# Feedback_Controller_Buck.net
KiCad netlist of a schematic drawn in Altium Designer
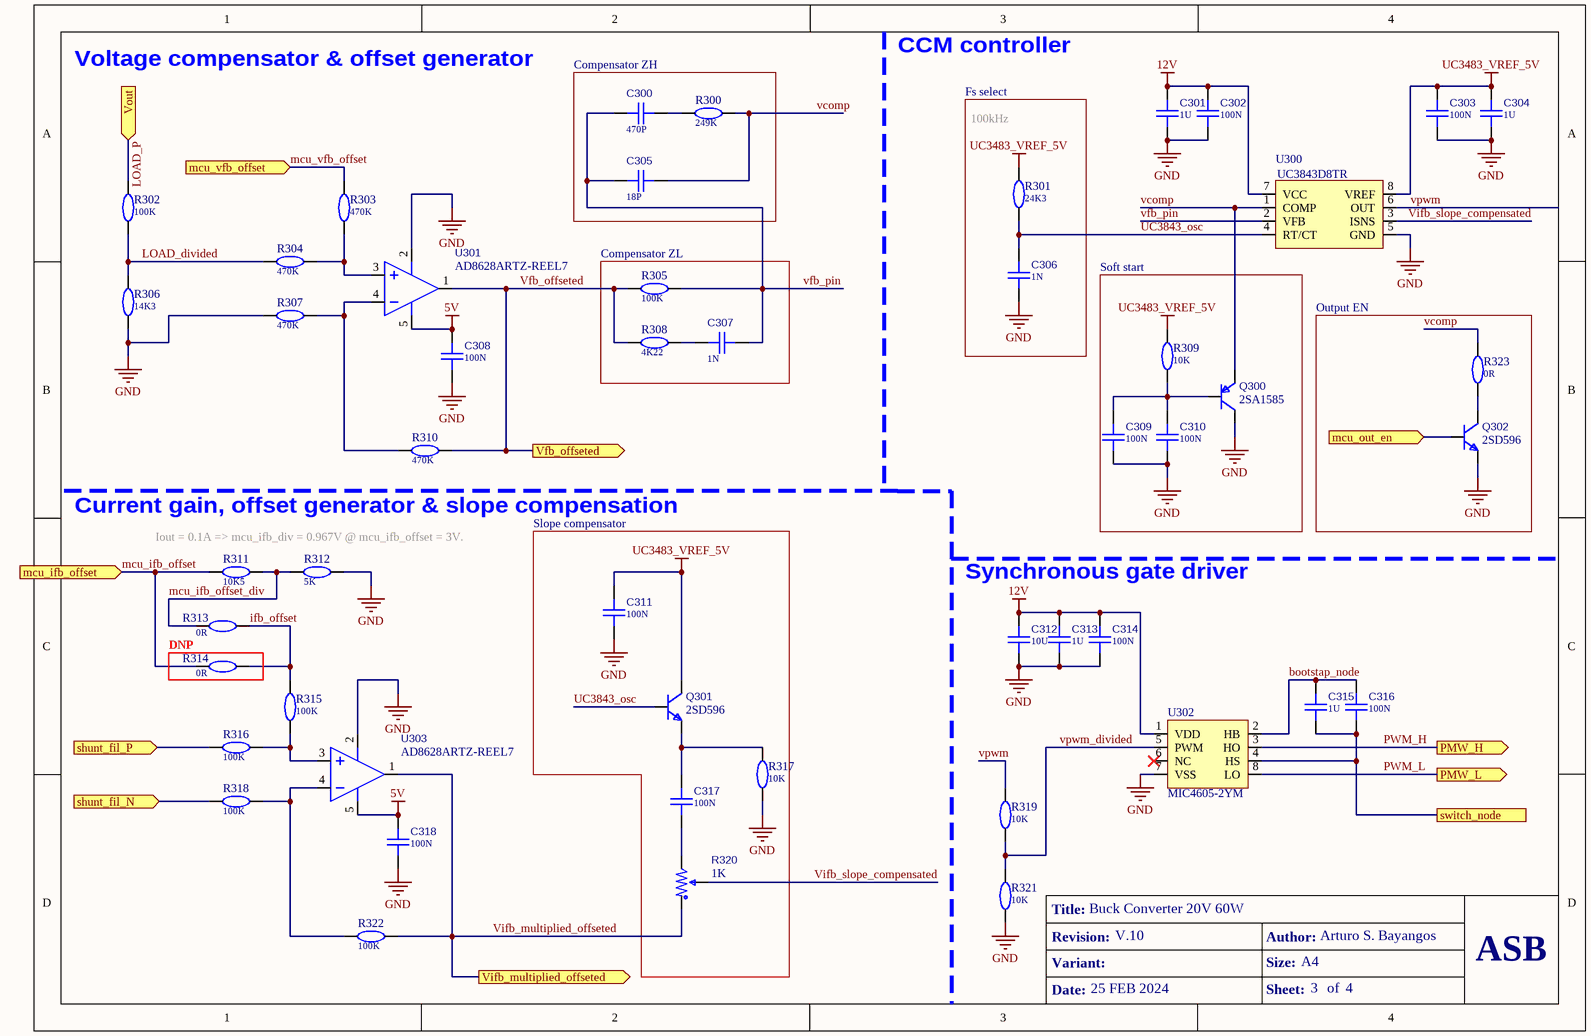
[diagram p0: Feedback_Controller_Buck.SchDoc]

(export (version "E")
  (design (tool "Eeschema 10.0.6"))
  (components
    (comp (ref "C300")
      (value "470P")
      (footprint "CAP_0603")
      (description "CAP 470P 0603 NPO 50V 2%")
      (fields (field (name "PART NUMBER") "CC0603GRNPO9BN471") (field (name "Comment") "CAPACITOR"))
      (libsource (lib "Altium_Library") (part "CAPACITOR"))
    )
    (comp (ref "C301")
      (value "1U")
      (footprint "CAP_0603")
      (description "CAP 1U 0603 X7R 25V 10%")
      (fields (field (name "PART NUMBER") "TMK107AB7105KAHT") (field (name "Comment") "CAPACITOR"))
      (libsource (lib "Altium_Library") (part "CAPACITOR"))
    )
    (comp (ref "C302")
      (value "100N")
      (footprint "CAP_0402")
      (description "CAP 100N 0402 X7R 50V 10%")
      (fields (field (name "PART NUMBER") "UMK105B7104KV-FR") (field (name "Comment") "CAPACITOR"))
      (libsource (lib "Altium_Library") (part "CAPACITOR"))
    )
    (comp (ref "C303")
      (value "100N")
      (footprint "CAP_0402")
      (description "CAP 100N 0402 X7R 50V 10%")
      (fields (field (name "PART NUMBER") "UMK105B7104KV-FR") (field (name "Comment") "CAPACITOR"))
      (libsource (lib "Altium_Library") (part "CAPACITOR"))
    )
    (comp (ref "C304")
      (value "1U")
      (footprint "CAP_0603")
      (description "CAP 1U 0603 X7R 25V 10%")
      (fields (field (name "PART NUMBER") "TMK107AB7105KAHT") (field (name "Comment") "CAPACITOR"))
      (libsource (lib "Altium_Library") (part "CAPACITOR"))
    )
    (comp (ref "C305")
      (value "18P")
      (footprint "CAP_0603")
      (description "CAP 18P 0603 NPO 50V 5%")
      (fields (field (name "PART NUMBER") "CC0603JRNPO9BN180") (field (name "Comment") "CAPACITOR"))
      (libsource (lib "Altium_Library") (part "CAPACITOR"))
    )
    (comp (ref "C306")
      (value "1N")
      (footprint "CAP_0603")
      (description "CAP 1N 0603 NPO 25V 2%")
      (fields (field (name "PART NUMBER") "CC0603GRNPO8BN102") (field (name "Comment") "CAPACITOR"))
      (libsource (lib "Altium_Library") (part "CAPACITOR"))
    )
    (comp (ref "C307")
      (value "1N")
      (footprint "CAP_0603")
      (description "CAP 1N 0603 NPO 25V 2%")
      (fields (field (name "PART NUMBER") "CC0603GRNPO8BN102") (field (name "Comment") "CAPACITOR"))
      (libsource (lib "Altium_Library") (part "CAPACITOR"))
    )
    (comp (ref "C308")
      (value "100N")
      (footprint "CAP_0402")
      (description "CAP 100N 0402 X7R 50V 10%")
      (fields (field (name "PART NUMBER") "UMK105B7104KV-FR") (field (name "Comment") "CAPACITOR"))
      (libsource (lib "Altium_Library") (part "CAPACITOR"))
    )
    (comp (ref "C309")
      (value "100N")
      (footprint "CAP_0402")
      (description "CAP 100N 0402 X7R 50V 10%")
      (fields (field (name "PART NUMBER") "UMK105B7104KV-FR") (field (name "Comment") "CAPACITOR"))
      (libsource (lib "Altium_Library") (part "CAPACITOR"))
    )
    (comp (ref "C310")
      (value "100N")
      (footprint "CAP_0402")
      (description "CAP 100N 0402 X7R 50V 10%")
      (fields (field (name "PART NUMBER") "UMK105B7104KV-FR") (field (name "Comment") "CAPACITOR"))
      (libsource (lib "Altium_Library") (part "CAPACITOR"))
    )
    (comp (ref "C311")
      (value "100N")
      (footprint "CAP_0402")
      (description "CAP 100N 0402 X7R 50V 10%")
      (fields (field (name "PART NUMBER") "UMK105B7104KV-FR") (field (name "Comment") "CAPACITOR"))
      (libsource (lib "Altium_Library") (part "CAPACITOR"))
    )
    (comp (ref "C312")
      (value "10U")
      (footprint "CAP_1210")
      (description "CAP 10U 1210 X7R 50V 10%")
      (fields (field (name "PART NUMBER") "UMK325AB7106KM-T") (field (name "Comment") "CAPACITOR"))
      (libsource (lib "Altium_Library") (part "CAPACITOR"))
    )
    (comp (ref "C313")
      (value "1U")
      (footprint "CAP_0603")
      (description "CAP 1U 0603 X7R 25V 10%")
      (fields (field (name "PART NUMBER") "TMK107AB7105KAHT") (field (name "Comment") "CAPACITOR"))
      (libsource (lib "Altium_Library") (part "CAPACITOR"))
    )
    (comp (ref "C314")
      (value "100N")
      (footprint "CAP_0402")
      (description "CAP 100N 0402 X7R 50V 10%")
      (fields (field (name "PART NUMBER") "UMK105B7104KV-FR") (field (name "Comment") "CAPACITOR"))
      (libsource (lib "Altium_Library") (part "CAPACITOR"))
    )
    (comp (ref "C315")
      (value "1U")
      (footprint "CAP_0603")
      (description "CAP 1U 0603 X7R 25V 10%")
      (fields (field (name "PART NUMBER") "TMK107AB7105KAHT") (field (name "Comment") "CAPACITOR"))
      (libsource (lib "Altium_Library") (part "CAPACITOR"))
    )
    (comp (ref "C316")
      (value "100N")
      (footprint "CAP_0402")
      (description "CAP 100N 0402 X7R 50V 10%")
      (fields (field (name "PART NUMBER") "UMK105B7104KV-FR") (field (name "Comment") "CAPACITOR"))
      (libsource (lib "Altium_Library") (part "CAPACITOR"))
    )
    (comp (ref "C317")
      (value "100N")
      (footprint "CAP_0402")
      (description "CAP 100N 0402 X7R 50V 10%")
      (fields (field (name "PART NUMBER") "UMK105B7104KV-FR") (field (name "Comment") "CAPACITOR"))
      (libsource (lib "Altium_Library") (part "CAPACITOR"))
    )
    (comp (ref "C318")
      (value "100N")
      (footprint "CAP_0402")
      (description "CAP 100N 0402 X7R 50V 10%")
      (fields (field (name "PART NUMBER") "UMK105B7104KV-FR") (field (name "Comment") "CAPACITOR"))
      (libsource (lib "Altium_Library") (part "CAPACITOR"))
    )
    (comp (ref "Q300")
      (value "2SA1585")
      (footprint "SOT-23")
      (description "PNP 2SA1585 SOT-23 20V 0.35W")
      (fields (field (name "POWER") "0.35W") (field (name "Comment") "BJT_PNP"))
      (libsource (lib "Altium_Library") (part "BJT_PNP"))
    )
    (comp (ref "Q301")
      (value "2SD596")
      (footprint "SOT-23")
      (description "NPN 2SD596 SOT-23 25V 0.2W")
      (fields (field (name "POWER") "0.2W") (field (name "Comment") "BJT_NPN"))
      (libsource (lib "Altium_Library") (part "BJT_NPN"))
    )
    (comp (ref "Q302")
      (value "2SD596")
      (footprint "SOT-23")
      (description "NPN 2SD596 SOT-23 25V 0.2W")
      (fields (field (name "POWER") "0.2W") (field (name "Comment") "BJT_NPN"))
      (libsource (lib "Altium_Library") (part "BJT_NPN"))
    )
    (comp (ref "R300")
      (value "249K")
      (footprint "RES_0603")
      (description "RES 249K 0603 1% 0.1W 75V")
      (fields (field (name "PART NUMBER") "FRC0603F2493TS") (field (name "Comment") "RESISTOR"))
      (libsource (lib "Altium_Library") (part "RESISTOR"))
    )
    (comp (ref "R301")
      (value "24K3")
      (footprint "RES_0603")
      (description "RES 24K3 0603 0.1% 0.1W 50V")
      (fields (field (name "PART NUMBER") "WF06H2432BTL") (field (name "Comment") "RESISTOR"))
      (libsource (lib "Altium_Library") (part "RESISTOR"))
    )
    (comp (ref "R302")
      (value "100K")
      (footprint "RES_0603")
      (description "RES 100K 0603 1% 0.1W 75V")
      (fields (field (name "PART NUMBER") "RC0603FR-07100KL") (field (name "Comment") "RESISTOR"))
      (libsource (lib "Altium_Library") (part "RESISTOR"))
    )
    (comp (ref "R303")
      (value "470K")
      (footprint "RES_0603")
      (description "RES 470K 0603 1% 0.1W 75V")
      (fields (field (name "PART NUMBER") "0603WAF4703T5E") (field (name "Comment") "RESISTOR"))
      (libsource (lib "Altium_Library") (part "RESISTOR"))
    )
    (comp (ref "R304")
      (value "470K")
      (footprint "RES_0603")
      (description "RES 470K 0603 1% 0.1W 75V")
      (fields (field (name "PART NUMBER") "0603WAF4703T5E") (field (name "Comment") "RESISTOR"))
      (libsource (lib "Altium_Library") (part "RESISTOR"))
    )
    (comp (ref "R305")
      (value "100K")
      (footprint "RES_0603")
      (description "RES 100K 0603 1% 0.1W 75V")
      (fields (field (name "PART NUMBER") "RC0603FR-07100KL") (field (name "Comment") "RESISTOR"))
      (libsource (lib "Altium_Library") (part "RESISTOR"))
    )
    (comp (ref "R306")
      (value "14K3")
      (footprint "RES_0603")
      (description "RES 14K3 0603 1% 0.1W 75V")
      (fields (field (name "PART NUMBER") "RT0603BRE0714K3L") (field (name "Comment") "RESISTOR"))
      (libsource (lib "Altium_Library") (part "RESISTOR"))
    )
    (comp (ref "R307")
      (value "470K")
      (footprint "RES_0603")
      (description "RES 470K 0603 1% 0.1W 75V")
      (fields (field (name "PART NUMBER") "0603WAF4703T5E") (field (name "Comment") "RESISTOR"))
      (libsource (lib "Altium_Library") (part "RESISTOR"))
    )
    (comp (ref "R308")
      (value "4K22")
      (footprint "RES_0603")
      (description "RES 4K22 0603 1% 0.1W 75V")
      (fields (field (name "PART NUMBER") "CRCW06034K22FKEA") (field (name "Comment") "RESISTOR"))
      (libsource (lib "Altium_Library") (part "RESISTOR"))
    )
    (comp (ref "R309")
      (value "10K")
      (footprint "RES_0603")
      (description "RES 10K 0603 0.1W 0.1% 75V")
      (fields (field (name "PART NUMBER") "ARG03BTC1002") (field (name "Comment") "RESISTOR"))
      (libsource (lib "Altium_Library") (part "RESISTOR"))
    )
    (comp (ref "R310")
      (value "470K")
      (footprint "RES_0603")
      (description "RES 470K 0603 1% 0.1W 75V")
      (fields (field (name "PART NUMBER") "0603WAF4703T5E") (field (name "Comment") "RESISTOR"))
      (libsource (lib "Altium_Library") (part "RESISTOR"))
    )
    (comp (ref "R311")
      (value "10K5")
      (footprint "RES_0402")
      (description "RES 10K5 0402 0.1% 0.625W 25V")
      (fields (field (name "PART NUMBER") "TC0250B1052TCC") (field (name "Comment") "RESISTOR"))
      (libsource (lib "Altium_Library") (part "RESISTOR"))
    )
    (comp (ref "R312")
      (value "5K")
      (footprint "RES_0402")
      (description "RES 5K 0402 0.1% 0.63W")
      (fields (field (name "PART NUMBER") "AR02BTC5001") (field (name "Comment") "RESISTOR"))
      (libsource (lib "Altium_Library") (part "RESISTOR"))
    )
    (comp (ref "R313")
      (value "0R")
      (footprint "RES_0402")
      (description "RES 0R 0402 1% 0.625W")
      (fields (field (name "PART NUMBER") "0402WGF0000TCE") (field (name "Comment") "RESISTOR"))
      (libsource (lib "Altium_Library") (part "RESISTOR"))
    )
    (comp (ref "R314")
      (value "0R")
      (footprint "RES_0402")
      (description "RES 0R 0402 1% 0.625W")
      (fields (field (name "PART NUMBER") "0402WGF0000TCE") (field (name "Comment") "RESISTOR"))
      (libsource (lib "Altium_Library") (part "RESISTOR"))
    )
    (comp (ref "R315")
      (value "100K")
      (footprint "RES_0603")
      (description "RES 100K 0603 1% 0.1W 75V")
      (fields (field (name "PART NUMBER") "RC0603FR-07100KL") (field (name "Comment") "RESISTOR"))
      (libsource (lib "Altium_Library") (part "RESISTOR"))
    )
    (comp (ref "R316")
      (value "100K")
      (footprint "RES_0603")
      (description "RES 100K 0603 1% 0.1W 75V")
      (fields (field (name "PART NUMBER") "RC0603FR-07100KL") (field (name "Comment") "RESISTOR"))
      (libsource (lib "Altium_Library") (part "RESISTOR"))
    )
    (comp (ref "R317")
      (value "10K")
      (footprint "RES_0603")
      (description "RES 10K 0603 0.1W 0.1% 75V")
      (fields (field (name "PART NUMBER") "ARG03BTC1002") (field (name "Comment") "RESISTOR"))
      (libsource (lib "Altium_Library") (part "RESISTOR"))
    )
    (comp (ref "R318")
      (value "100K")
      (footprint "RES_0603")
      (description "RES 100K 0603 1% 0.1W 75V")
      (fields (field (name "PART NUMBER") "RC0603FR-07100KL") (field (name "Comment") "RESISTOR"))
      (libsource (lib "Altium_Library") (part "RESISTOR"))
    )
    (comp (ref "R319")
      (value "10K")
      (footprint "RES_0603")
      (description "RES 10K 0603 0.1W 0.1% 75V")
      (fields (field (name "PART NUMBER") "ARG03BTC1002") (field (name "Comment") "RESISTOR"))
      (libsource (lib "Altium_Library") (part "RESISTOR"))
    )
    (comp (ref "R320")
      (value "1K")
      (footprint "RES_GF063P1-B102")
      (description "RES POT 1K TH 20%")
      (fields (field (name "PART NUMBER") "GF063P1-B102") (field (name "Comment") "RESISTOR_POT"))
      (libsource (lib "Altium_Library") (part "RESISTOR_POT"))
    )
    (comp (ref "R321")
      (value "10K")
      (footprint "RES_0603")
      (description "RES 10K 0603 0.1W 0.1% 75V")
      (fields (field (name "PART NUMBER") "ARG03BTC1002") (field (name "Comment") "RESISTOR"))
      (libsource (lib "Altium_Library") (part "RESISTOR"))
    )
    (comp (ref "R322")
      (value "100K")
      (footprint "RES_0603")
      (description "RES 100K 0603 1% 0.1W 75V")
      (fields (field (name "PART NUMBER") "RC0603FR-07100KL") (field (name "Comment") "RESISTOR"))
      (libsource (lib "Altium_Library") (part "RESISTOR"))
    )
    (comp (ref "R323")
      (value "0R")
      (footprint "RES_0402")
      (description "RES 0R 0402 1% 0.625W")
      (fields (field (name "PART NUMBER") "0402WGF0000TCE") (field (name "Comment") "RESISTOR"))
      (libsource (lib "Altium_Library") (part "RESISTOR"))
    )
    (comp (ref "U300")
      (value "UC3843D8TR")
      (footprint "SOIC-8")
      (description "IC UC3843D8TR SOIC-8 PWM-CONTROLLER")
      (fields (field (name "Comment") "PWM-CONTROLLER_8P"))
      (libsource (lib "Altium_Library") (part "PWM-CONTROLLER_8P"))
    )
    (comp (ref "U301")
      (value "AD8628ARTZ-REEL7")
      (footprint "SOT-23-5")
      (description "OPAMP AD8628ARTZ-REEL7 SOT-23-5 2.5MHz")
      (fields (field (name "Comment") "OPAMP_1"))
      (libsource (lib "Altium_Library") (part "OPAMP_1"))
    )
    (comp (ref "U302")
      (value "MIC4605-2YM")
      (footprint "SOIC-8")
      (description "GATEDRVR MIC4605-2YM SOIC-8 HALF-BRIDGE  5.5V-16V")
      (fields (field (name "Comment") "GATEDRIVE_8P_SINGLE-PWM"))
      (libsource (lib "Altium_Library") (part "GATEDRIVE_8P_SINGLE-PWM"))
    )
    (comp (ref "U303")
      (value "AD8628ARTZ-REEL7")
      (footprint "SOT-23-5")
      (description "OPAMP AD8628ARTZ-REEL7 SOT-23-5 2.5MHz")
      (fields (field (name "Comment") "OPAMP_1"))
      (libsource (lib "Altium_Library") (part "OPAMP_1"))
    )
  )
  (nets
    (net (code "1") (name "/LOAD_P") (class "Default")
      (node (ref "R302") (pin "2") (pinfunction "2_2") (pintype "passive"))
    )
    (net (code "2") (name "/LOAD_divided") (class "Default")
      (node (ref "R302") (pin "1") (pinfunction "1_1") (pintype "passive"))
      (node (ref "R304") (pin "1") (pinfunction "1_1") (pintype "passive"))
      (node (ref "R306") (pin "2") (pinfunction "2_2") (pintype "passive"))
    )
    (net (code "3") (name "/PWM_H") (class "Default")
      (node (ref "U302") (pin "3") (pinfunction "HO_3") (pintype "passive"))
    )
    (net (code "4") (name "/PWM_L") (class "Default")
      (node (ref "U302") (pin "8") (pinfunction "LO_8") (pintype "passive"))
    )
    (net (code "5") (name "/UC3843_osc") (class "Default")
      (node (ref "C306") (pin "1") (pinfunction "1_1") (pintype "passive"))
      (node (ref "Q301") (pin "1") (pinfunction "B_1") (pintype "passive"))
      (node (ref "R301") (pin "1") (pinfunction "1_1") (pintype "passive"))
      (node (ref "U300") (pin "4") (pinfunction "RT/CT_4") (pintype "passive"))
    )
    (net (code "6") (name "/Vfb_offseted") (class "Default")
      (node (ref "R305") (pin "1") (pinfunction "1_1") (pintype "passive"))
      (node (ref "R308") (pin "1") (pinfunction "1_1") (pintype "passive"))
      (node (ref "R310") (pin "2") (pinfunction "2_2") (pintype "passive"))
      (node (ref "U301") (pin "1") (pinfunction "OUT_1") (pintype "passive"))
    )
    (net (code "7") (name "/Vifb_multiplied_offseted") (class "Default")
      (node (ref "R320") (pin "1") (pinfunction "1_1") (pintype "passive"))
      (node (ref "R322") (pin "2") (pinfunction "2_2") (pintype "passive"))
      (node (ref "U303") (pin "1") (pinfunction "OUT_1") (pintype "passive"))
    )
    (net (code "8") (name "/Vifb_slope_compensated") (class "Default")
      (node (ref "R320") (pin "2") (pinfunction "2_2") (pintype "passive"))
      (node (ref "U300") (pin "3") (pinfunction "ISNS_3") (pintype "passive"))
    )
    (net (code "9") (name "/bootstap_node") (class "Default")
      (node (ref "C315") (pin "2") (pinfunction "2_2") (pintype "passive"))
      (node (ref "C316") (pin "1") (pinfunction "1_1") (pintype "passive"))
      (node (ref "U302") (pin "2") (pinfunction "HB_2") (pintype "passive"))
    )
    (net (code "10") (name "/ifb_offset") (class "Default")
      (node (ref "R313") (pin "2") (pinfunction "2_2") (pintype "passive"))
      (node (ref "R314") (pin "2") (pinfunction "2_2") (pintype "passive"))
      (node (ref "R315") (pin "2") (pinfunction "2_2") (pintype "passive"))
    )
    (net (code "11") (name "/mcu_ifb_offset") (class "Default")
      (node (ref "R311") (pin "1") (pinfunction "1_1") (pintype "passive"))
      (node (ref "R314") (pin "1") (pinfunction "1_1") (pintype "passive"))
    )
    (net (code "12") (name "/mcu_ifb_offset_div") (class "Default")
      (node (ref "R311") (pin "2") (pinfunction "2_2") (pintype "passive"))
      (node (ref "R312") (pin "1") (pinfunction "1_1") (pintype "passive"))
      (node (ref "R313") (pin "1") (pinfunction "1_1") (pintype "passive"))
    )
    (net (code "13") (name "/mcu_out_en") (class "Default")
      (node (ref "Q302") (pin "1") (pinfunction "B_1") (pintype "passive"))
    )
    (net (code "14") (name "/mcu_vfb_offset") (class "Default")
      (node (ref "R303") (pin "2") (pinfunction "2_2") (pintype "passive"))
    )
    (net (code "15") (name "/shunt_fil_N") (class "Default")
      (node (ref "R318") (pin "1") (pinfunction "1_1") (pintype "passive"))
    )
    (net (code "16") (name "/shunt_fil_P") (class "Default")
      (node (ref "R316") (pin "1") (pinfunction "1_1") (pintype "passive"))
    )
    (net (code "17") (name "/switch_node") (class "Default")
      (node (ref "C315") (pin "1") (pinfunction "1_1") (pintype "passive"))
      (node (ref "C316") (pin "2") (pinfunction "2_2") (pintype "passive"))
      (node (ref "U302") (pin "4") (pinfunction "HS_4") (pintype "passive"))
    )
    (net (code "18") (name "/vcomp") (class "Default")
      (node (ref "C305") (pin "2") (pinfunction "2_2") (pintype "passive"))
      (node (ref "Q300") (pin "2") (pinfunction "E_2") (pintype "passive"))
      (node (ref "R300") (pin "2") (pinfunction "2_2") (pintype "passive"))
      (node (ref "R323") (pin "2") (pinfunction "2_2") (pintype "passive"))
      (node (ref "U300") (pin "1") (pinfunction "COMP_1") (pintype "passive"))
    )
    (net (code "19") (name "/vfb_pin") (class "Default")
      (node (ref "C300") (pin "1") (pinfunction "1_1") (pintype "passive"))
      (node (ref "C305") (pin "1") (pinfunction "1_1") (pintype "passive"))
      (node (ref "C307") (pin "2") (pinfunction "2_2") (pintype "passive"))
      (node (ref "R305") (pin "2") (pinfunction "2_2") (pintype "passive"))
      (node (ref "U300") (pin "2") (pinfunction "VFB_2") (pintype "passive"))
    )
    (net (code "20") (name "/vpwm") (class "Default")
      (node (ref "R319") (pin "2") (pinfunction "2_2") (pintype "passive"))
      (node (ref "U300") (pin "6") (pinfunction "OUT_6") (pintype "passive"))
    )
    (net (code "21") (name "/vpwm_divided") (class "Default")
      (node (ref "R319") (pin "1") (pinfunction "1_1") (pintype "passive"))
      (node (ref "R321") (pin "2") (pinfunction "2_2") (pintype "passive"))
      (node (ref "U302") (pin "5") (pinfunction "PWM_5") (pintype "passive"))
    )
    (net (code "22") (name "5V") (class "Default")
      (node (ref "C308") (pin "2") (pinfunction "2_2") (pintype "passive"))
      (node (ref "C318") (pin "2") (pinfunction "2_2") (pintype "passive"))
      (node (ref "U301") (pin "5") (pinfunction "+V_5") (pintype "passive"))
      (node (ref "U303") (pin "5") (pinfunction "+V_5") (pintype "passive"))
    )
    (net (code "23") (name "12V") (class "Default")
      (node (ref "C301") (pin "2") (pinfunction "2_2") (pintype "passive"))
      (node (ref "C302") (pin "2") (pinfunction "2_2") (pintype "passive"))
      (node (ref "C312") (pin "2") (pinfunction "2_2") (pintype "passive"))
      (node (ref "C313") (pin "1") (pinfunction "1_1") (pintype "passive"))
      (node (ref "C314") (pin "2") (pinfunction "2_2") (pintype "passive"))
      (node (ref "U300") (pin "7") (pinfunction "VCC_7") (pintype "passive"))
      (node (ref "U302") (pin "1") (pinfunction "VDD_1") (pintype "passive"))
    )
    (net (code "24") (name "GND") (class "Default")
      (node (ref "C301") (pin "1") (pinfunction "1_1") (pintype "passive"))
      (node (ref "C302") (pin "1") (pinfunction "1_1") (pintype "passive"))
      (node (ref "C303") (pin "1") (pinfunction "1_1") (pintype "passive"))
      (node (ref "C304") (pin "1") (pinfunction "1_1") (pintype "passive"))
      (node (ref "C306") (pin "2") (pinfunction "2_2") (pintype "passive"))
      (node (ref "C308") (pin "1") (pinfunction "1_1") (pintype "passive"))
      (node (ref "C309") (pin "1") (pinfunction "1_1") (pintype "passive"))
      (node (ref "C310") (pin "1") (pinfunction "1_1") (pintype "passive"))
      (node (ref "C311") (pin "1") (pinfunction "1_1") (pintype "passive"))
      (node (ref "C312") (pin "1") (pinfunction "1_1") (pintype "passive"))
      (node (ref "C313") (pin "2") (pinfunction "2_2") (pintype "passive"))
      (node (ref "C314") (pin "1") (pinfunction "1_1") (pintype "passive"))
      (node (ref "C318") (pin "1") (pinfunction "1_1") (pintype "passive"))
      (node (ref "Q300") (pin "3") (pinfunction "C_3") (pintype "passive"))
      (node (ref "Q302") (pin "2") (pinfunction "E_2") (pintype "passive"))
      (node (ref "R306") (pin "1") (pinfunction "1_1") (pintype "passive"))
      (node (ref "R307") (pin "1") (pinfunction "1_1") (pintype "passive"))
      (node (ref "R312") (pin "2") (pinfunction "2_2") (pintype "passive"))
      (node (ref "R317") (pin "1") (pinfunction "1_1") (pintype "passive"))
      (node (ref "R321") (pin "1") (pinfunction "1_1") (pintype "passive"))
      (node (ref "U300") (pin "5") (pinfunction "GND_5") (pintype "passive"))
      (node (ref "U301") (pin "2") (pinfunction "-V_2") (pintype "passive"))
      (node (ref "U302") (pin "7") (pinfunction "VSS_7") (pintype "passive"))
      (node (ref "U303") (pin "2") (pinfunction "-V_2") (pintype "passive"))
    )
    (net (code "25") (name "Net-(C300-Pad2)") (class "Default")
      (node (ref "C300") (pin "2") (pinfunction "2_2") (pintype "passive"))
      (node (ref "R300") (pin "1") (pinfunction "1_1") (pintype "passive"))
    )
    (net (code "26") (name "Net-(C307-Pad1)") (class "Default")
      (node (ref "C307") (pin "1") (pinfunction "1_1") (pintype "passive"))
      (node (ref "R308") (pin "2") (pinfunction "2_2") (pintype "passive"))
    )
    (net (code "27") (name "Net-(C317-Pad1)") (class "Default")
      (node (ref "C317") (pin "1") (pinfunction "1_1") (pintype "passive"))
      (node (ref "R320") (pin "3") (pinfunction "3_3") (pintype "passive"))
    )
    (net (code "28") (name "Net-(Q300-B)") (class "Default")
      (node (ref "C309") (pin "2") (pinfunction "2_2") (pintype "passive"))
      (node (ref "C310") (pin "2") (pinfunction "2_2") (pintype "passive"))
      (node (ref "Q300") (pin "1") (pinfunction "B_1") (pintype "passive"))
      (node (ref "R309") (pin "1") (pinfunction "1_1") (pintype "passive"))
    )
    (net (code "29") (name "Net-(Q301-E)") (class "Default")
      (node (ref "C317") (pin "2") (pinfunction "2_2") (pintype "passive"))
      (node (ref "Q301") (pin "2") (pinfunction "E_2") (pintype "passive"))
      (node (ref "R317") (pin "2") (pinfunction "2_2") (pintype "passive"))
    )
    (net (code "30") (name "Net-(Q302-C)") (class "Default")
      (node (ref "Q302") (pin "3") (pinfunction "C_3") (pintype "passive"))
      (node (ref "R323") (pin "1") (pinfunction "1_1") (pintype "passive"))
    )
    (net (code "31") (name "Net-(U301-+IN)") (class "Default")
      (node (ref "R303") (pin "1") (pinfunction "1_1") (pintype "passive"))
      (node (ref "R304") (pin "2") (pinfunction "2_2") (pintype "passive"))
      (node (ref "U301") (pin "3") (pinfunction "+IN_3") (pintype "passive"))
    )
    (net (code "32") (name "Net-(U301--IN)") (class "Default")
      (node (ref "R307") (pin "2") (pinfunction "2_2") (pintype "passive"))
      (node (ref "R310") (pin "1") (pinfunction "1_1") (pintype "passive"))
      (node (ref "U301") (pin "4") (pinfunction "-IN_4") (pintype "passive"))
    )
    (net (code "33") (name "Net-(U303-+IN)") (class "Default")
      (node (ref "R315") (pin "1") (pinfunction "1_1") (pintype "passive"))
      (node (ref "R316") (pin "2") (pinfunction "2_2") (pintype "passive"))
      (node (ref "U303") (pin "3") (pinfunction "+IN_3") (pintype "passive"))
    )
    (net (code "34") (name "Net-(U303--IN)") (class "Default")
      (node (ref "R318") (pin "2") (pinfunction "2_2") (pintype "passive"))
      (node (ref "R322") (pin "1") (pinfunction "1_1") (pintype "passive"))
      (node (ref "U303") (pin "4") (pinfunction "-IN_4") (pintype "passive"))
    )
    (net (code "35") (name "UC3483_VREF_5V") (class "Default")
      (node (ref "C303") (pin "2") (pinfunction "2_2") (pintype "passive"))
      (node (ref "C304") (pin "2") (pinfunction "2_2") (pintype "passive"))
      (node (ref "C311") (pin "2") (pinfunction "2_2") (pintype "passive"))
      (node (ref "Q301") (pin "3") (pinfunction "C_3") (pintype "passive"))
      (node (ref "R301") (pin "2") (pinfunction "2_2") (pintype "passive"))
      (node (ref "R309") (pin "2") (pinfunction "2_2") (pintype "passive"))
      (node (ref "U300") (pin "8") (pinfunction "VREF_8") (pintype "passive"))
    )
    (net (code "36") (name "unconnected-(U302-NC-Pad6)") (class "Default")
      (node (ref "U302") (pin "6") (pinfunction "NC_6") (pintype "passive+no_connect"))
    )
  )
)
